# nfc-epd-afe.net
KiCad netlist of a schematic drawn in Altium Designer
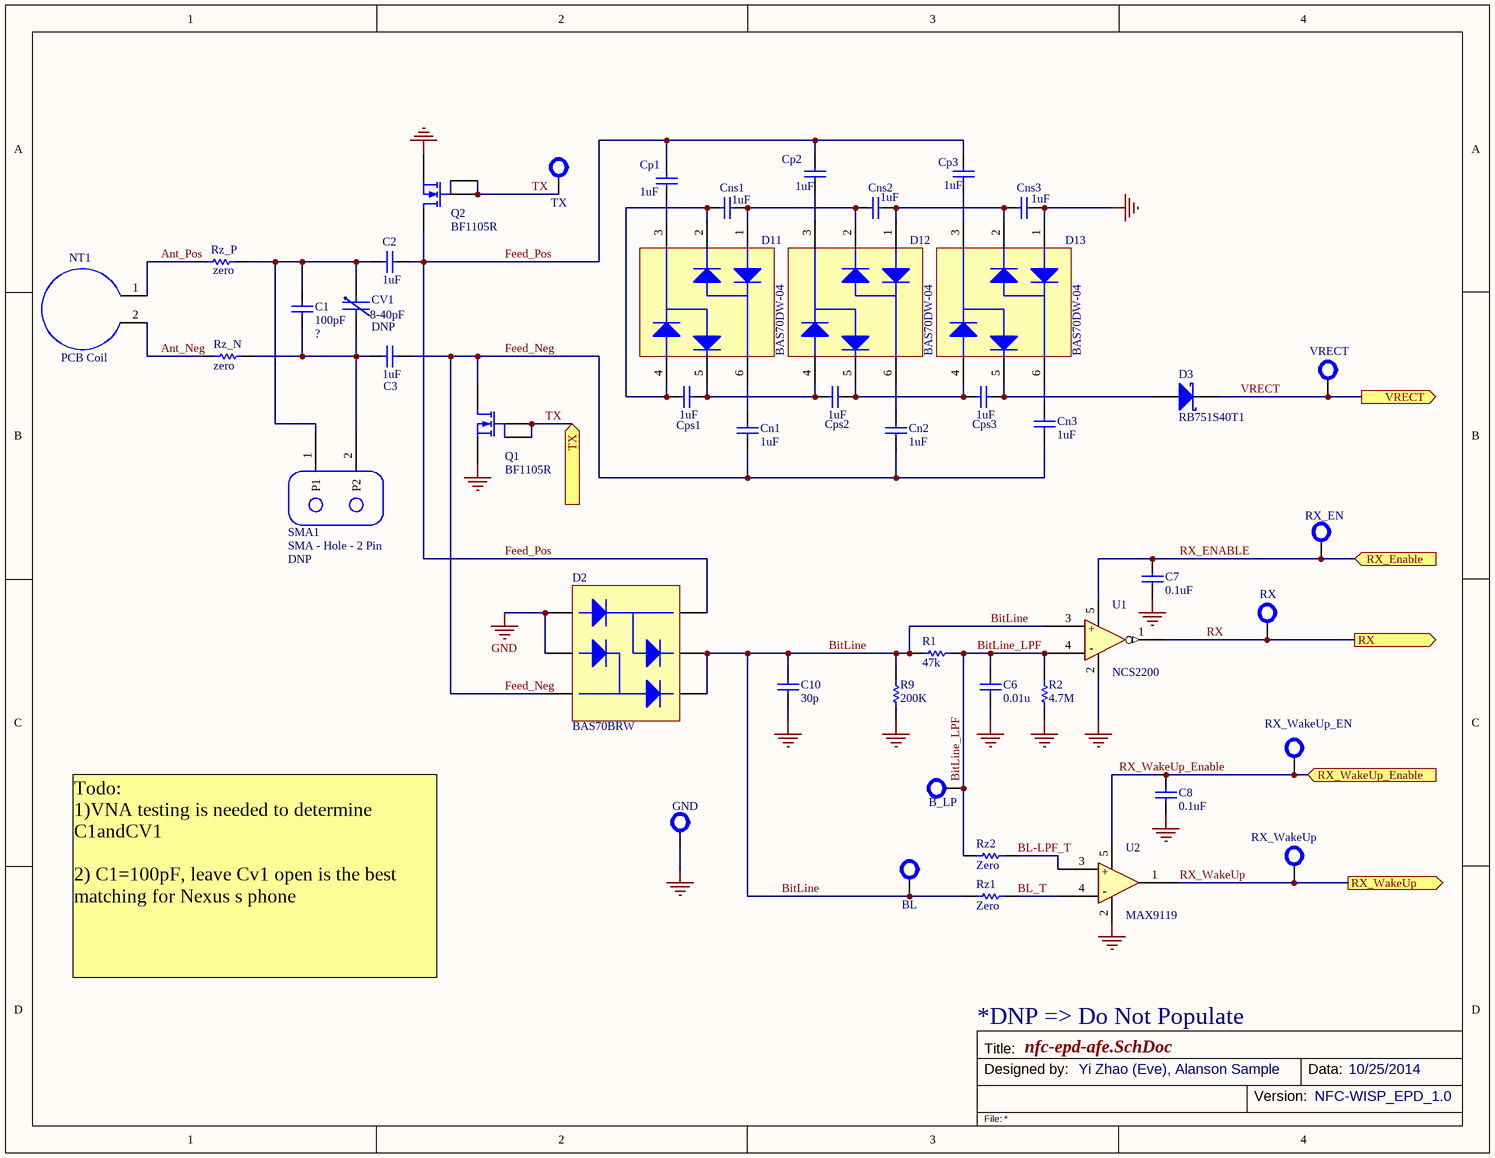
[diagram p0: nfc-epd-afe.SchDoc]

(export (version "E")
  (design (tool "Eeschema 10.0.6"))
  (components
    (comp (ref "BL")
      (value "Test Point")
      (footprint "Test Point - Small")
      (description "Test Point, large or small foot prints")
      (fields
        (field (name "DIGI-KEY PART NUMBER") "Example: 5000K-ND, 5012K-ND, Surface mount 5015KCT-ND")
        (field (name "MANUFACTURER PART NUMBER") "Example: 5000, 5013")
      )
      (libsource (lib "WISP_AD10") (part "Test Point"))
    )
    (comp (ref "B_LP")
      (value "Test Point")
      (footprint "Test Point - Small")
      (description "Test Point, large or small foot prints")
      (fields
        (field (name "DIGI-KEY PART NUMBER") "Example: 5000K-ND, 5012K-ND, Surface mount 5015KCT-ND")
        (field (name "MANUFACTURER PART NUMBER") "Example: 5000, 5013")
      )
      (libsource (lib "WISP_AD10") (part "Test Point"))
    )
    (comp (ref "C1")
      (value "?")
      (footprint "0603")
      (description "Ceramic Capacitor (Surface Mount)")
      (fields
        (field (name "MANUFACTURER") "Generic Ceramic Chip Cap (TBD)")
        (field (name "NOTE") "100pF")
        (field (name "Comment") "Cap")
      )
      (libsource (lib "WISP_AD10") (part "Cap"))
    )
    (comp (ref "C2")
      (value "1uF")
      (footprint "0603")
      (description "Ceramic Capacitor (Surface Mount)")
      (fields (field (name "MANUFACTURER") "Generic Ceramic Chip Cap (TBD)") (field (name "Comment") "Cap"))
      (libsource (lib "WISP_AD10") (part "Cap"))
    )
    (comp (ref "C3")
      (value "1uF")
      (footprint "0603")
      (description "Ceramic Capacitor (Surface Mount)")
      (fields (field (name "MANUFACTURER") "Generic Ceramic Chip Cap (TBD)") (field (name "Comment") "Cap"))
      (libsource (lib "WISP_AD10") (part "Cap"))
    )
    (comp (ref "C6")
      (value "0.01u")
      (footprint "0603")
      (description "Ceramic Capacitor (Surface Mount)")
      (fields (field (name "MANUFACTURER") "Generic Ceramic Chip Cap (TBD)") (field (name "Comment") "Cap"))
      (libsource (lib "WISP_AD10") (part "Cap"))
    )
    (comp (ref "C7")
      (value "0.1uF")
      (footprint "0603")
      (description "Ceramic Capacitor (Surface Mount)")
      (fields (field (name "MANUFACTURER") "Generic Ceramic Chip Cap (TBD)") (field (name "Comment") "Cap"))
      (libsource (lib "WISP_AD10") (part "Cap"))
    )
    (comp (ref "C8")
      (value "0.1uF")
      (footprint "0603")
      (description "Ceramic Capacitor (Surface Mount)")
      (fields (field (name "MANUFACTURER") "Generic Ceramic Chip Cap (TBD)") (field (name "Comment") "Cap"))
      (libsource (lib "WISP_AD10") (part "Cap"))
    )
    (comp (ref "C10")
      (value "30p")
      (footprint "0603")
      (description "Ceramic Capacitor (Surface Mount)")
      (fields (field (name "MANUFACTURER") "Generic Ceramic Chip Cap (TBD)") (field (name "Comment") "Cap"))
      (libsource (lib "WISP_AD10") (part "Cap"))
    )
    (comp (ref "Cn1")
      (value "1uF")
      (footprint "0603")
      (description "Ceramic Capacitor (Surface Mount)")
      (fields (field (name "MANUFACTURER") "Generic Ceramic Chip Cap (TBD)") (field (name "Comment") "Cap"))
      (libsource (lib "WISP_AD10") (part "Cap"))
    )
    (comp (ref "Cn2")
      (value "1uF")
      (footprint "0603")
      (description "Ceramic Capacitor (Surface Mount)")
      (fields (field (name "MANUFACTURER") "Generic Ceramic Chip Cap (TBD)") (field (name "Comment") "Cap"))
      (libsource (lib "WISP_AD10") (part "Cap"))
    )
    (comp (ref "Cn3")
      (value "1uF")
      (footprint "0603")
      (description "Ceramic Capacitor (Surface Mount)")
      (fields (field (name "MANUFACTURER") "Generic Ceramic Chip Cap (TBD)") (field (name "Comment") "Cap"))
      (libsource (lib "WISP_AD10") (part "Cap"))
    )
    (comp (ref "Cns1")
      (value "1uF")
      (footprint "0603")
      (description "Ceramic Capacitor (Surface Mount)")
      (fields (field (name "MANUFACTURER") "Generic Ceramic Chip Cap (TBD)") (field (name "Comment") "Cap"))
      (libsource (lib "WISP_AD10") (part "Cap"))
    )
    (comp (ref "Cns2")
      (value "1uF")
      (footprint "0603")
      (description "Ceramic Capacitor (Surface Mount)")
      (fields (field (name "MANUFACTURER") "Generic Ceramic Chip Cap (TBD)") (field (name "Comment") "Cap"))
      (libsource (lib "WISP_AD10") (part "Cap"))
    )
    (comp (ref "Cns3")
      (value "1uF")
      (footprint "0603")
      (description "Ceramic Capacitor (Surface Mount)")
      (fields (field (name "MANUFACTURER") "Generic Ceramic Chip Cap (TBD)") (field (name "Comment") "Cap"))
      (libsource (lib "WISP_AD10") (part "Cap"))
    )
    (comp (ref "Cp1")
      (value "1uF")
      (footprint "0603")
      (description "Ceramic Capacitor (Surface Mount)")
      (fields (field (name "MANUFACTURER") "Generic Ceramic Chip Cap (TBD)") (field (name "Comment") "Cap"))
      (libsource (lib "WISP_AD10") (part "Cap"))
    )
    (comp (ref "Cp2")
      (value "1uF")
      (footprint "0603")
      (description "Ceramic Capacitor (Surface Mount)")
      (fields (field (name "MANUFACTURER") "Generic Ceramic Chip Cap (TBD)") (field (name "Comment") "Cap"))
      (libsource (lib "WISP_AD10") (part "Cap"))
    )
    (comp (ref "Cp3")
      (value "1uF")
      (footprint "0603")
      (description "Ceramic Capacitor (Surface Mount)")
      (fields (field (name "MANUFACTURER") "Generic Ceramic Chip Cap (TBD)") (field (name "Comment") "Cap"))
      (libsource (lib "WISP_AD10") (part "Cap"))
    )
    (comp (ref "Cps1")
      (value "1uF")
      (footprint "0603")
      (description "Ceramic Capacitor (Surface Mount)")
      (fields (field (name "MANUFACTURER") "Generic Ceramic Chip Cap (TBD)") (field (name "Comment") "Cap"))
      (libsource (lib "WISP_AD10") (part "Cap"))
    )
    (comp (ref "Cps2")
      (value "1uF")
      (footprint "0603")
      (description "Ceramic Capacitor (Surface Mount)")
      (fields (field (name "MANUFACTURER") "Generic Ceramic Chip Cap (TBD)") (field (name "Comment") "Cap"))
      (libsource (lib "WISP_AD10") (part "Cap"))
    )
    (comp (ref "Cps3")
      (value "1uF")
      (footprint "0603")
      (description "Ceramic Capacitor (Surface Mount)")
      (fields (field (name "MANUFACTURER") "Generic Ceramic Chip Cap (TBD)") (field (name "Comment") "Cap"))
      (libsource (lib "WISP_AD10") (part "Cap"))
    )
    (comp (ref "CV1")
      (value "8-40pF")
      (footprint "Var-Cap - GKY40056")
      (description "Var-Cap Sprague-Goodman GKY40056")
      (fields
        (field (name "DIGI-KEY PART NUMBER") "SG9013CT-ND")
        (field (name "MANUFACTURER PART NUMBER") "GKY40056")
        (field (name "NOTE") "DNP")
      )
      (libsource (lib "WISP_AD10") (part "Var-Cap/603"))
    )
    (comp (ref "D2")
      (value "BAS70BRW")
      (footprint "SOT-363")
      (description "Diode Array - 2 Pair Series Connection")
      (fields
        (field (name "MANUFACTURER") "Diodes Inc")
        (field (name "MANUFACTURER PART NUMBER") "BAS70BRW-7-F")
      )
      (libsource (lib "WISP_AD10") (part "Diode - Array_2"))
    )
    (comp (ref "D3")
      (value "RB751S40T1")
      (footprint "SOD-523")
      (description "Schottky Diode")
      (fields (field (name "PUBLISHER") "Altium Limited"))
      (libsource (lib "WISP_AD10") (part "RB751S40T1"))
    )
    (comp (ref "D11")
      (value "BAS70DW-04")
      (footprint "SOT-363")
      (description "Diode Array - 2 Pair Series Connection")
      (fields
        (field (name "MANUFACTURER") "Diodes Inc")
        (field (name "DIGI-KEY PART NUMBER") "BAS70DW-04FDICT-ND")
      )
      (libsource (lib "WISP_AD10") (part "Diode - Array_2_1"))
    )
    (comp (ref "D12")
      (value "BAS70DW-04")
      (footprint "SOT-363")
      (description "Diode Array - 2 Pair Series Connection")
      (fields
        (field (name "MANUFACTURER") "Diodes Inc")
        (field (name "DIGI-KEY PART NUMBER") "BAS70DW-04FDICT-ND")
      )
      (libsource (lib "WISP_AD10") (part "Diode - Array_2_1"))
    )
    (comp (ref "D13")
      (value "BAS70DW-04")
      (footprint "SOT-363")
      (description "Diode Array - 2 Pair Series Connection")
      (fields
        (field (name "MANUFACTURER") "Diodes Inc")
        (field (name "DIGI-KEY PART NUMBER") "BAS70DW-04FDICT-ND")
      )
      (libsource (lib "WISP_AD10") (part "Diode - Array_2_1"))
    )
    (comp (ref "GND0")
      (value "GND")
      (footprint "Test Point - Small")
      (description "Test Point, large or small foot prints")
      (fields
        (field (name "DIGI-KEY PART NUMBER") "Example: 5000K-ND, 5012K-ND, Surface mount 5015KCT-ND")
        (field (name "MANUFACTURER PART NUMBER") "Example: 5000, 5013")
      )
      (libsource (lib "WISP_AD10") (part "Test Point"))
    )
    (comp (ref "NT1")
      (value "PCB Coil")
      (footprint "Net Tie - 50mil")
      (description "Hand draw coil symbol based on a 'Net Tie'")
      (libsource (lib "WISP_AD10") (part "Net Tie - Coil"))
    )
    (comp (ref "Q1")
      (value "BF1105R")
      (footprint "SOT-143R")
      (description "SOT-143R, N-Channel Dual-Gate Mos-Fets MOSFET")
      (fields
        (field (name "DIGI-KEY PART NUMBER") "BF1105R,215-ND")
        (field (name "MANUFACTURER PART NUMBER") "BF1105R,215")
      )
      (libsource (lib "WISP_AD10") (part "BF1105R"))
    )
    (comp (ref "Q2")
      (value "BF1105R")
      (footprint "SOT-143R")
      (description "SOT-143R, N-Channel Dual-Gate Mos-Fets MOSFET")
      (fields
        (field (name "MANUFACTURER PART NUMBER") "BF1105R,215")
        (field (name "MANUFACTURER") "NXP Semiconductors")
      )
      (libsource (lib "WISP_AD10") (part "BF1105R"))
    )
    (comp (ref "R1")
      (value "47k")
      (footprint "0603")
      (description "Chip Resistor (Surface Mount)")
      (fields (field (name "MANUFACTURER") "Generic Chip Res (TBD)") (field (name "Comment") "Res"))
      (libsource (lib "WISP_AD10") (part "Res"))
    )
    (comp (ref "R2")
      (value "4.7M")
      (footprint "0603")
      (description "Chip Resistor (Surface Mount)")
      (fields (field (name "MANUFACTURER") "Generic Chip Res (TBD)") (field (name "Comment") "Res"))
      (libsource (lib "WISP_AD10") (part "Res"))
    )
    (comp (ref "R9")
      (value "200K")
      (footprint "0603")
      (description "Chip Resistor (Surface Mount)")
      (fields (field (name "MANUFACTURER") "Generic Chip Res (TBD)") (field (name "Comment") "Res"))
      (libsource (lib "WISP_AD10") (part "Res"))
    )
    (comp (ref "RX")
      (value "Test Point")
      (footprint "Test Point - Small")
      (description "Test Point, large or small foot prints")
      (fields
        (field (name "DIGI-KEY PART NUMBER") "Example: 5000K-ND, 5012K-ND, Surface mount 5015KCT-ND")
        (field (name "MANUFACTURER PART NUMBER") "Example: 5000, 5013")
      )
      (libsource (lib "WISP_AD10") (part "Test Point"))
    )
    (comp (ref "RX_EN")
      (value "Test Point")
      (footprint "Test Point - Small")
      (description "Test Point, large or small foot prints")
      (fields
        (field (name "DIGI-KEY PART NUMBER") "Example: 5000K-ND, 5012K-ND, Surface mount 5015KCT-ND")
        (field (name "MANUFACTURER PART NUMBER") "Example: 5000, 5013")
      )
      (libsource (lib "WISP_AD10") (part "Test Point"))
    )
    (comp (ref "RX_WakeUp")
      (value "Test Point")
      (footprint "Test Point - Small")
      (description "Test Point, large or small foot prints")
      (fields
        (field (name "DIGI-KEY PART NUMBER") "Example: 5000K-ND, 5012K-ND, Surface mount 5015KCT-ND")
        (field (name "MANUFACTURER PART NUMBER") "Example: 5000, 5013")
      )
      (libsource (lib "WISP_AD10") (part "Test Point"))
    )
    (comp (ref "RX_WakeUp_EN")
      (value "Test Point")
      (footprint "Test Point - Small")
      (description "Test Point, large or small foot prints")
      (fields
        (field (name "DIGI-KEY PART NUMBER") "Example: 5000K-ND, 5012K-ND, Surface mount 5015KCT-ND")
        (field (name "MANUFACTURER PART NUMBER") "Example: 5000, 5013")
      )
      (libsource (lib "WISP_AD10") (part "Test Point"))
    )
    (comp (ref "Rz1")
      (value "Zero")
      (footprint "0603")
      (description "Chip Resistor (Surface Mount)")
      (fields
        (field (name "MANUFACTURER") "Generic Chip Res (TBD)")
        (field (name "MANUFACTURER PART NUMBER") "RC0603FR-070RL")
      )
      (libsource (lib "WREL_AD10") (part "Res"))
    )
    (comp (ref "Rz2")
      (value "Zero")
      (footprint "0603")
      (description "Chip Resistor (Surface Mount)")
      (fields
        (field (name "MANUFACTURER") "Generic Chip Res (TBD)")
        (field (name "MANUFACTURER PART NUMBER") "RC0603FR-070RL")
      )
      (libsource (lib "WREL_AD10") (part "Res"))
    )
    (comp (ref "Rz_N")
      (value "zero")
      (footprint "0603")
      (description "Chip Resistor (Surface Mount)")
      (fields
        (field (name "MANUFACTURER") "Generic Chip Res (TBD)")
        (field (name "MANUFACTURER PART NUMBER") "RC0603FR-070RL")
      )
      (libsource (lib "WISP_AD10") (part "Res"))
    )
    (comp (ref "Rz_P")
      (value "zero")
      (footprint "0603")
      (description "Chip Resistor (Surface Mount)")
      (fields
        (field (name "MANUFACTURER") "Generic Chip Res (TBD)")
        (field (name "MANUFACTURER PART NUMBER") "RC0603FR-070RL")
      )
      (libsource (lib "WISP_AD10") (part "Res"))
    )
    (comp (ref "SMA1")
      (value "SMA - Hole - 2 Pin")
      (footprint "SMA - Hole - 2 Pin")
      (description "Two pin SMA connector wisp")
      (fields (field (name "NOTE") "DNP"))
      (libsource (lib "WISP_AD10") (part "SMA - Hole - 2 Pin"))
    )
    (comp (ref "TX")
      (value "Test Point")
      (footprint "Test Point - Small")
      (description "Test Point, large or small foot prints")
      (fields
        (field (name "DIGI-KEY PART NUMBER") "Example: 5000K-ND, 5012K-ND, Surface mount 5015KCT-ND")
        (field (name "MANUFACTURER PART NUMBER") "Example: 5000, 5013")
      )
      (libsource (lib "WISP_AD10") (part "Test Point"))
    )
    (comp (ref "U1")
      (value "NCS2200")
      (footprint "SC70-5")
      (description "Comparator: On Semi 10uA Comparator")
      (fields
        (field (name "DIGI-KEY PART NUMBER") "NCS2200SQ2T2GOSTR-ND")
        (field (name "MANUFACTURER") "ON Semiconductor")
      )
      (libsource (lib "WISP_AD10") (part "NCS2200"))
    )
    (comp (ref "U2")
      (value "MAX9119")
      (footprint "SC70-5")
      (description "IC COMPARATOR BTR SC70-5, 350nA")
      (fields
        (field (name "DIGI-KEY PART NUMBER") "MAX9119EXK+TCT-ND")
        (field (name "MANUFACTURER") "Maxim Integrated")
      )
      (libsource (lib "WISP_AD10") (part "MAX9119"))
    )
    (comp (ref "VRECT")
      (value "Test Point")
      (footprint "Test Point - Small")
      (description "Test Point, large or small foot prints")
      (fields
        (field (name "DIGI-KEY PART NUMBER") "Example: 5000K-ND, 5012K-ND, Surface mount 5015KCT-ND")
        (field (name "MANUFACTURER PART NUMBER") "Example: 5000, 5013")
      )
      (libsource (lib "WISP_AD10") (part "Test Point"))
    )
  )
  (nets
    (net (code "1") (name "/Ant_Neg") (class "Default")
      (node (ref "NT1") (pin "2") (pinfunction "N2_2") (pintype "passive"))
      (node (ref "Rz_N") (pin "1") (pinfunction "1_1") (pintype "passive"))
    )
    (net (code "2") (name "/Ant_Pos") (class "Default")
      (node (ref "NT1") (pin "1") (pinfunction "N1_1") (pintype "passive"))
      (node (ref "Rz_P") (pin "1") (pinfunction "1_1") (pintype "passive"))
    )
    (net (code "3") (name "/BL-LPF_T") (class "Default")
      (node (ref "Rz2") (pin "2") (pinfunction "2_2") (pintype "passive"))
      (node (ref "U2") (pin "3") (pinfunction "IN+_3") (pintype "passive"))
    )
    (net (code "4") (name "/BL_T") (class "Default")
      (node (ref "Rz1") (pin "2") (pinfunction "2_2") (pintype "passive"))
      (node (ref "U2") (pin "4") (pinfunction "In-_4") (pintype "passive"))
    )
    (net (code "5") (name "/BitLine") (class "Default")
      (node (ref "BL") (pin "0") (pinfunction "0_0") (pintype "passive"))
      (node (ref "C10") (pin "1") (pinfunction "1_1") (pintype "passive"))
      (node (ref "D2") (pin "4") (pinfunction "C2_4") (pintype "passive"))
      (node (ref "D2") (pin "5") (pinfunction "C1_5") (pintype "passive"))
      (node (ref "R1") (pin "1") (pinfunction "1_1") (pintype "passive"))
      (node (ref "R9") (pin "1") (pinfunction "1_1") (pintype "passive"))
      (node (ref "Rz1") (pin "1") (pinfunction "1_1") (pintype "passive"))
      (node (ref "U1") (pin "3") (pinfunction "IN+_3") (pintype "passive"))
    )
    (net (code "6") (name "/BitLine_LPF") (class "Default")
      (node (ref "B_LP") (pin "0") (pinfunction "0_0") (pintype "passive"))
      (node (ref "C6") (pin "1") (pinfunction "1_1") (pintype "passive"))
      (node (ref "R1") (pin "2") (pinfunction "2_2") (pintype "passive"))
      (node (ref "R2") (pin "1") (pinfunction "1_1") (pintype "passive"))
      (node (ref "Rz2") (pin "1") (pinfunction "1_1") (pintype "passive"))
      (node (ref "U1") (pin "4") (pinfunction "In-_4") (pintype "passive"))
    )
    (net (code "7") (name "/Feed_Neg") (class "Default")
      (node (ref "C3") (pin "2") (pinfunction "2_2") (pintype "passive"))
      (node (ref "Cn1") (pin "1") (pinfunction "1_1") (pintype "passive"))
      (node (ref "Cn2") (pin "1") (pinfunction "1_1") (pintype "passive"))
      (node (ref "Cn3") (pin "1") (pinfunction "1_1") (pintype "passive"))
      (node (ref "D2") (pin "3") (pinfunction "AC2_3") (pintype "passive"))
      (node (ref "Q1") (pin "2") (pinfunction "D_2") (pintype "passive"))
    )
    (net (code "8") (name "/Feed_Pos") (class "Default")
      (node (ref "C2") (pin "2") (pinfunction "2_2") (pintype "passive"))
      (node (ref "Cp1") (pin "2") (pinfunction "2_2") (pintype "passive"))
      (node (ref "Cp2") (pin "2") (pinfunction "2_2") (pintype "passive"))
      (node (ref "Cp3") (pin "2") (pinfunction "2_2") (pintype "passive"))
      (node (ref "D2") (pin "6") (pinfunction "AC1_6") (pintype "passive"))
      (node (ref "Q2") (pin "2") (pinfunction "D_2") (pintype "passive"))
    )
    (net (code "9") (name "/RX") (class "Default")
      (node (ref "RX") (pin "0") (pinfunction "0_0") (pintype "passive"))
      (node (ref "U1") (pin "1") (pinfunction "OUT_1") (pintype "output"))
    )
    (net (code "10") (name "/RX_ENABLE") (class "Default")
      (node (ref "C7") (pin "1") (pinfunction "1_1") (pintype "passive"))
      (node (ref "RX_EN") (pin "0") (pinfunction "0_0") (pintype "passive"))
      (node (ref "U1") (pin "5") (pinfunction "VDD_5") (pintype "passive"))
    )
    (net (code "11") (name "/RX_WakeUp") (class "Default")
      (node (ref "RX_WakeUp") (pin "0") (pinfunction "0_0") (pintype "passive"))
      (node (ref "U2") (pin "1") (pinfunction "OUT_1") (pintype "passive"))
    )
    (net (code "12") (name "/RX_WakeUp_Enable") (class "Default")
      (node (ref "C8") (pin "1") (pinfunction "1_1") (pintype "passive"))
      (node (ref "RX_WakeUp_EN") (pin "0") (pinfunction "0_0") (pintype "passive"))
      (node (ref "U2") (pin "5") (pinfunction "VCC_5") (pintype "passive"))
    )
    (net (code "13") (name "/TX") (class "Default")
      (node (ref "Q1") (pin "3") (pinfunction "G_3") (pintype "passive"))
      (node (ref "Q1") (pin "4") (pinfunction "G_4") (pintype "passive"))
      (node (ref "Q2") (pin "3") (pinfunction "G_3") (pintype "passive"))
      (node (ref "Q2") (pin "4") (pinfunction "G_4") (pintype "passive"))
      (node (ref "TX") (pin "0") (pinfunction "0_0") (pintype "passive"))
    )
    (net (code "14") (name "/VRECT") (class "Default")
      (node (ref "D3") (pin "2") (pinfunction "C_2") (pintype "passive"))
      (node (ref "VRECT") (pin "0") (pinfunction "0_0") (pintype "passive"))
    )
    (net (code "15") (name "GND") (class "Default")
      (node (ref "C10") (pin "2") (pinfunction "2_2") (pintype "passive"))
      (node (ref "C6") (pin "2") (pinfunction "2_2") (pintype "passive"))
      (node (ref "C7") (pin "2") (pinfunction "2_2") (pintype "passive"))
      (node (ref "C8") (pin "2") (pinfunction "2_2") (pintype "passive"))
      (node (ref "Cns3") (pin "1") (pinfunction "1_1") (pintype "passive"))
      (node (ref "D13") (pin "1") (pinfunction "A1_1") (pintype "passive"))
      (node (ref "D2") (pin "1") (pinfunction "A1_1") (pintype "passive"))
      (node (ref "D2") (pin "2") (pinfunction "A2_2") (pintype "passive"))
      (node (ref "GND0") (pin "0") (pinfunction "0_0") (pintype "passive"))
      (node (ref "Q1") (pin "1") (pinfunction "S_1") (pintype "passive"))
      (node (ref "Q2") (pin "1") (pinfunction "S_1") (pintype "passive"))
      (node (ref "R2") (pin "2") (pinfunction "2_2") (pintype "passive"))
      (node (ref "R9") (pin "2") (pinfunction "2_2") (pintype "passive"))
      (node (ref "U1") (pin "2") (pinfunction "Gnd_2") (pintype "power_in"))
      (node (ref "U2") (pin "2") (pinfunction "VEE_2") (pintype "passive"))
    )
    (net (code "16") (name "Net-(D11-A1)") (class "Default")
      (node (ref "Cns1") (pin "1") (pinfunction "1_1") (pintype "passive"))
      (node (ref "Cns2") (pin "2") (pinfunction "2_2") (pintype "passive"))
      (node (ref "D11") (pin "1") (pinfunction "A1_1") (pintype "passive"))
      (node (ref "D12") (pin "2") (pinfunction "C1_2") (pintype "passive"))
    )
    (net (code "17") (name "Net-(D11-A2)") (class "Default")
      (node (ref "Cns1") (pin "2") (pinfunction "2_2") (pintype "passive"))
      (node (ref "Cps1") (pin "2") (pinfunction "2_2") (pintype "passive"))
      (node (ref "D11") (pin "2") (pinfunction "C1_2") (pintype "passive"))
      (node (ref "D11") (pin "4") (pinfunction "A2_4") (pintype "passive"))
    )
    (net (code "18") (name "Net-(D11-AC)") (class "Default")
      (node (ref "Cn1") (pin "2") (pinfunction "2_2") (pintype "passive"))
      (node (ref "D11") (pin "6") (pinfunction "AC_6") (pintype "passive"))
    )
    (net (code "19") (name "Net-(D11-AC2)") (class "Default")
      (node (ref "Cp1") (pin "1") (pinfunction "1_1") (pintype "passive"))
      (node (ref "D11") (pin "3") (pinfunction "AC2_3") (pintype "passive"))
    )
    (net (code "20") (name "Net-(D11-C2)") (class "Default")
      (node (ref "Cps1") (pin "1") (pinfunction "1_1") (pintype "passive"))
      (node (ref "Cps2") (pin "2") (pinfunction "2_2") (pintype "passive"))
      (node (ref "D11") (pin "5") (pinfunction "C2_5") (pintype "passive"))
      (node (ref "D12") (pin "4") (pinfunction "A2_4") (pintype "passive"))
    )
    (net (code "21") (name "Net-(D12-A1)") (class "Default")
      (node (ref "Cns2") (pin "1") (pinfunction "1_1") (pintype "passive"))
      (node (ref "Cns3") (pin "2") (pinfunction "2_2") (pintype "passive"))
      (node (ref "D12") (pin "1") (pinfunction "A1_1") (pintype "passive"))
      (node (ref "D13") (pin "2") (pinfunction "C1_2") (pintype "passive"))
    )
    (net (code "22") (name "Net-(D12-AC)") (class "Default")
      (node (ref "Cn2") (pin "2") (pinfunction "2_2") (pintype "passive"))
      (node (ref "D12") (pin "6") (pinfunction "AC_6") (pintype "passive"))
    )
    (net (code "23") (name "Net-(D12-AC2)") (class "Default")
      (node (ref "Cp2") (pin "1") (pinfunction "1_1") (pintype "passive"))
      (node (ref "D12") (pin "3") (pinfunction "AC2_3") (pintype "passive"))
    )
    (net (code "24") (name "Net-(D12-C2)") (class "Default")
      (node (ref "Cps2") (pin "1") (pinfunction "1_1") (pintype "passive"))
      (node (ref "Cps3") (pin "2") (pinfunction "2_2") (pintype "passive"))
      (node (ref "D12") (pin "5") (pinfunction "C2_5") (pintype "passive"))
      (node (ref "D13") (pin "4") (pinfunction "A2_4") (pintype "passive"))
    )
    (net (code "25") (name "Net-(D13-AC)") (class "Default")
      (node (ref "Cn3") (pin "2") (pinfunction "2_2") (pintype "passive"))
      (node (ref "D13") (pin "6") (pinfunction "AC_6") (pintype "passive"))
    )
    (net (code "26") (name "Net-(D13-AC2)") (class "Default")
      (node (ref "Cp3") (pin "1") (pinfunction "1_1") (pintype "passive"))
      (node (ref "D13") (pin "3") (pinfunction "AC2_3") (pintype "passive"))
    )
    (net (code "27") (name "Net-(D13-C2)") (class "Default")
      (node (ref "Cps3") (pin "1") (pinfunction "1_1") (pintype "passive"))
      (node (ref "D13") (pin "5") (pinfunction "C2_5") (pintype "passive"))
      (node (ref "D3") (pin "1") (pinfunction "A_1") (pintype "passive"))
    )
    (net (code "28") (name "Net-(SMA1-P1)") (class "Default")
      (node (ref "C1") (pin "1") (pinfunction "1_1") (pintype "passive"))
      (node (ref "C2") (pin "1") (pinfunction "1_1") (pintype "passive"))
      (node (ref "CV1") (pin "1") (pinfunction "1_1") (pintype "passive"))
      (node (ref "Rz_P") (pin "2") (pinfunction "2_2") (pintype "passive"))
      (node (ref "SMA1") (pin "1") (pinfunction "P1_1") (pintype "passive"))
    )
    (net (code "29") (name "Net-(SMA1-P2)") (class "Default")
      (node (ref "C1") (pin "2") (pinfunction "2_2") (pintype "passive"))
      (node (ref "C3") (pin "1") (pinfunction "1_1") (pintype "passive"))
      (node (ref "CV1") (pin "2") (pinfunction "2_2") (pintype "passive"))
      (node (ref "Rz_N") (pin "2") (pinfunction "2_2") (pintype "passive"))
      (node (ref "SMA1") (pin "2") (pinfunction "P2_2") (pintype "passive"))
    )
  )
)
